# infinity_mirror.net
KiCad netlist of a schematic drawn in EAGLE
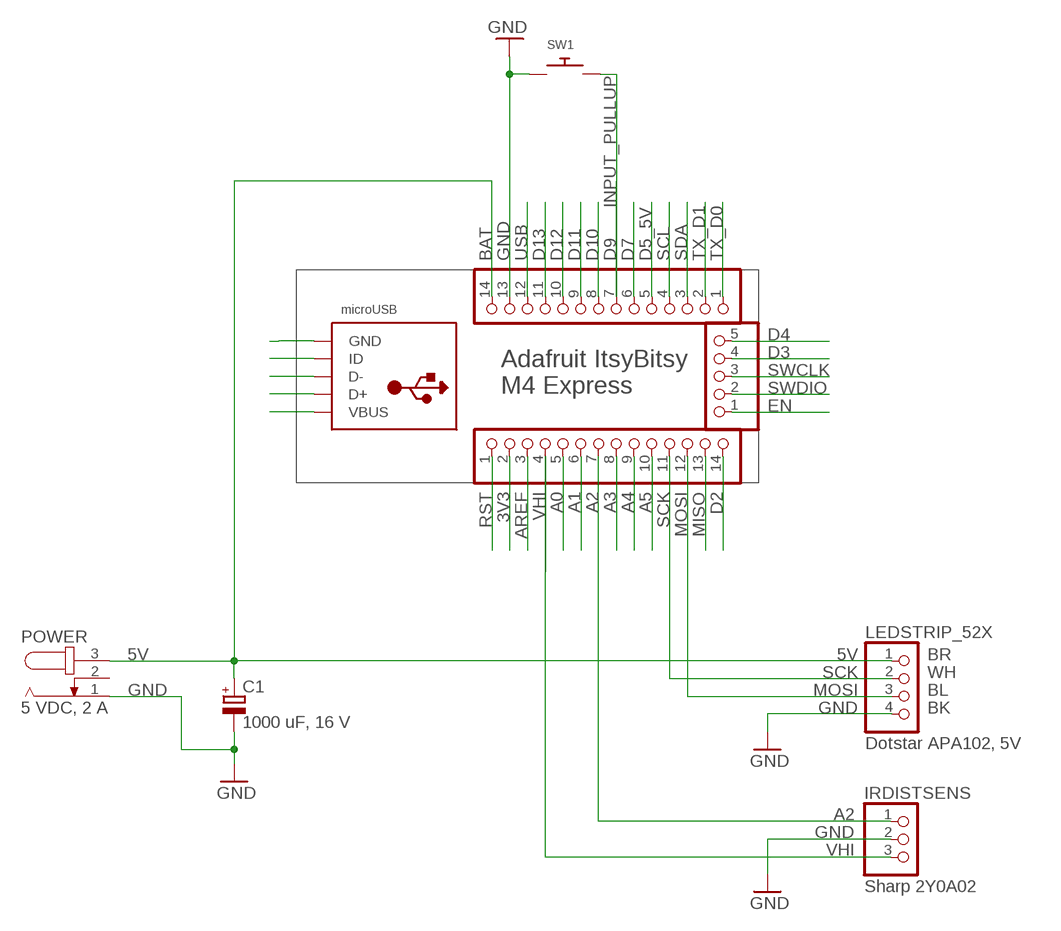
[diagram p0: schematic, sheet 1]

(export (version "E")
  (design (tool "Eeschema 10.0.6"))
  (components
    (comp (ref "C1")
      (value "1000 uF, 16 V")
      (footprint "eagle-import:E3,5-8")
      (libsource (lib "eagle-import") (part "CPOL-EUE3.5-8"))
    )
    (comp (ref "IRDISTSENS")
      (value "Sharp 2Y0A02")
      (footprint "eagle-import:1X03")
      (libsource (lib "eagle-import") (part "PINHD-1X3"))
    )
    (comp (ref "JP1")
      (value "PINHD-1X14")
      (footprint "eagle-import:1X14")
      (libsource (lib "eagle-import") (part "PINHD-1X14"))
    )
    (comp (ref "JP2")
      (value "PINHD-1X14")
      (footprint "eagle-import:1X14")
      (libsource (lib "eagle-import") (part "PINHD-1X14"))
    )
    (comp (ref "JP4")
      (value "PINHD-1X5")
      (footprint "eagle-import:1X05")
      (libsource (lib "eagle-import") (part "PINHD-1X5"))
    )
    (comp (ref "LEDSTRIP_52X")
      (value "Dotstar APA102, 5V")
      (footprint "eagle-import:1X04")
      (libsource (lib "eagle-import") (part "PINHD-1X4"))
    )
    (comp (ref "POWER")
      (value "5 VDC, 2 A")
      (footprint "eagle-import:SPC4078")
      (libsource (lib "eagle-import") (part "JACK-PLUG1"))
    )
    (comp (ref "SW1")
      (value "SWITCH_PUSHBUTTONSOFTTOUCHSMD_SJ")
      (footprint "eagle-import:PUSHBUTTON_SMD_SJ")
      (libsource (lib "eagle-import") (part "SWITCH_PUSHBUTTONSOFTTOUCHSMD_SJ"))
    )
    (comp (ref "X3")
      (value "microUSB")
      (footprint "eagle-import:4UCONN_20329_V2")
      (libsource (lib "eagle-import") (part "USB_MICRO_20329_V2"))
    )
  )
  (nets
    (net (code "1") (name "/3V3") (class "Default")
      (node (ref "JP2") (pin "2") (pinfunction "2_2") (pintype "passive"))
    )
    (net (code "2") (name "/5V") (class "Default")
      (node (ref "C1") (pin "+") (pinfunction "+_+") (pintype "passive"))
      (node (ref "JP1") (pin "14") (pinfunction "14_14") (pintype "passive"))
      (node (ref "LEDSTRIP_52X") (pin "1") (pinfunction "1_1") (pintype "passive"))
      (node (ref "POWER") (pin "3") (pinfunction "3_3") (pintype "passive"))
    )
    (net (code "3") (name "/A0") (class "Default")
      (node (ref "JP2") (pin "5") (pinfunction "5_5") (pintype "passive"))
    )
    (net (code "4") (name "/A1") (class "Default")
      (node (ref "JP2") (pin "6") (pinfunction "6_6") (pintype "passive"))
    )
    (net (code "5") (name "/A2") (class "Default")
      (node (ref "IRDISTSENS") (pin "1") (pinfunction "1_1") (pintype "passive"))
      (node (ref "JP2") (pin "7") (pinfunction "7_7") (pintype "passive"))
    )
    (net (code "6") (name "/A3") (class "Default")
      (node (ref "JP2") (pin "8") (pinfunction "8_8") (pintype "passive"))
    )
    (net (code "7") (name "/A4") (class "Default")
      (node (ref "JP2") (pin "9") (pinfunction "9_9") (pintype "passive"))
    )
    (net (code "8") (name "/A5") (class "Default")
      (node (ref "JP2") (pin "10") (pinfunction "10_10") (pintype "passive"))
    )
    (net (code "9") (name "/AREF") (class "Default")
      (node (ref "JP2") (pin "3") (pinfunction "3_3") (pintype "passive"))
    )
    (net (code "10") (name "/D2") (class "Default")
      (node (ref "JP2") (pin "14") (pinfunction "14_14") (pintype "passive"))
    )
    (net (code "11") (name "/D3") (class "Default")
      (node (ref "JP4") (pin "4") (pinfunction "4_4") (pintype "passive"))
    )
    (net (code "12") (name "/D4") (class "Default")
      (node (ref "JP4") (pin "5") (pinfunction "5_5") (pintype "passive"))
    )
    (net (code "13") (name "/D5_5V") (class "Default")
      (node (ref "JP1") (pin "5") (pinfunction "5_5") (pintype "passive"))
    )
    (net (code "14") (name "/D7") (class "Default")
      (node (ref "JP1") (pin "6") (pinfunction "6_6") (pintype "passive"))
    )
    (net (code "15") (name "/D9") (class "Default")
      (node (ref "JP1") (pin "7") (pinfunction "7_7") (pintype "passive"))
      (node (ref "SW1") (pin "P$2") (pinfunction "P$2_P$2") (pintype "passive"))
    )
    (net (code "16") (name "/D10") (class "Default")
      (node (ref "JP1") (pin "8") (pinfunction "8_8") (pintype "passive"))
    )
    (net (code "17") (name "/D11") (class "Default")
      (node (ref "JP1") (pin "9") (pinfunction "9_9") (pintype "passive"))
    )
    (net (code "18") (name "/D12") (class "Default")
      (node (ref "JP1") (pin "10") (pinfunction "10_10") (pintype "passive"))
    )
    (net (code "19") (name "/D13") (class "Default")
      (node (ref "JP1") (pin "11") (pinfunction "11_11") (pintype "passive"))
    )
    (net (code "20") (name "/EN") (class "Default")
      (node (ref "JP4") (pin "1") (pinfunction "1_1") (pintype "passive"))
    )
    (net (code "21") (name "/MISO") (class "Default")
      (node (ref "JP2") (pin "13") (pinfunction "13_13") (pintype "passive"))
    )
    (net (code "22") (name "/MOSI") (class "Default")
      (node (ref "JP2") (pin "12") (pinfunction "12_12") (pintype "passive"))
      (node (ref "LEDSTRIP_52X") (pin "3") (pinfunction "3_3") (pintype "passive"))
    )
    (net (code "23") (name "/RST") (class "Default")
      (node (ref "JP2") (pin "1") (pinfunction "1_1") (pintype "passive"))
    )
    (net (code "24") (name "/SCK") (class "Default")
      (node (ref "JP2") (pin "11") (pinfunction "11_11") (pintype "passive"))
      (node (ref "LEDSTRIP_52X") (pin "2") (pinfunction "2_2") (pintype "passive"))
    )
    (net (code "25") (name "/SCL") (class "Default")
      (node (ref "JP1") (pin "4") (pinfunction "4_4") (pintype "passive"))
    )
    (net (code "26") (name "/SDA") (class "Default")
      (node (ref "JP1") (pin "3") (pinfunction "3_3") (pintype "passive"))
    )
    (net (code "27") (name "/SWCLK") (class "Default")
      (node (ref "JP4") (pin "3") (pinfunction "3_3") (pintype "passive"))
    )
    (net (code "28") (name "/SWDIO") (class "Default")
      (node (ref "JP4") (pin "2") (pinfunction "2_2") (pintype "passive"))
    )
    (net (code "29") (name "/TX_D0") (class "Default")
      (node (ref "JP1") (pin "1") (pinfunction "1_1") (pintype "passive"))
    )
    (net (code "30") (name "/TX_D1") (class "Default")
      (node (ref "JP1") (pin "2") (pinfunction "2_2") (pintype "passive"))
    )
    (net (code "31") (name "/USB") (class "Default")
      (node (ref "JP1") (pin "12") (pinfunction "12_12") (pintype "passive"))
    )
    (net (code "32") (name "/VHI") (class "Default")
      (node (ref "IRDISTSENS") (pin "3") (pinfunction "3_3") (pintype "passive"))
      (node (ref "JP2") (pin "4") (pinfunction "4_4") (pintype "passive"))
    )
    (net (code "33") (name "GND") (class "Default")
      (node (ref "C1") (pin "-") (pinfunction "-_-") (pintype "passive"))
      (node (ref "IRDISTSENS") (pin "2") (pinfunction "2_2") (pintype "passive"))
      (node (ref "JP1") (pin "13") (pinfunction "13_13") (pintype "passive"))
      (node (ref "LEDSTRIP_52X") (pin "4") (pinfunction "4_4") (pintype "passive"))
      (node (ref "POWER") (pin "1") (pinfunction "1_1") (pintype "passive"))
      (node (ref "SW1") (pin "P$1") (pinfunction "P$1_P$1") (pintype "passive"))
    )
    (net (code "34") (name "Net-(X3-GND-PadBASE@1)") (class "Default")
      (node (ref "X3") (pin "BASE@1") (pinfunction "GND_BASE@1") (pintype "power_in"))
      (node (ref "X3") (pin "BASE@2") (pinfunction "GND_BASE@2") (pintype "power_in"))
      (node (ref "X3") (pin "GND") (pinfunction "GND_GND") (pintype "power_in"))
      (node (ref "X3") (pin "SPRT@1") (pinfunction "GND_SPRT@1") (pintype "power_in"))
      (node (ref "X3") (pin "SPRT@2") (pinfunction "GND_SPRT@2") (pintype "power_in"))
      (node (ref "X3") (pin "SPRT@3") (pinfunction "GND_SPRT@3") (pintype "power_in"))
      (node (ref "X3") (pin "SPRT@4") (pinfunction "GND_SPRT@4") (pintype "power_in"))
    )
    (net (code "35") (name "unconnected-(POWER-Pad2)") (class "Default")
      (node (ref "POWER") (pin "2") (pinfunction "2_2") (pintype "passive"))
    )
    (net (code "36") (name "unconnected-(X3-PadD+)") (class "Default")
      (node (ref "X3") (pin "D+") (pinfunction "D+_D+") (pintype "bidirectional"))
    )
    (net (code "37") (name "unconnected-(X3-PadD-)") (class "Default")
      (node (ref "X3") (pin "D-") (pinfunction "D-_D-") (pintype "bidirectional"))
    )
    (net (code "38") (name "unconnected-(X3-PadID)") (class "Default")
      (node (ref "X3") (pin "ID") (pinfunction "ID_ID") (pintype "bidirectional"))
    )
    (net (code "39") (name "unconnected-(X3-PadVBUS)") (class "Default")
      (node (ref "X3") (pin "VBUS") (pinfunction "VBUS_VBUS") (pintype "power_in"))
    )
  )
)
